# Current_Sense_2.net
KiCad netlist of a schematic drawn in Altium Designer
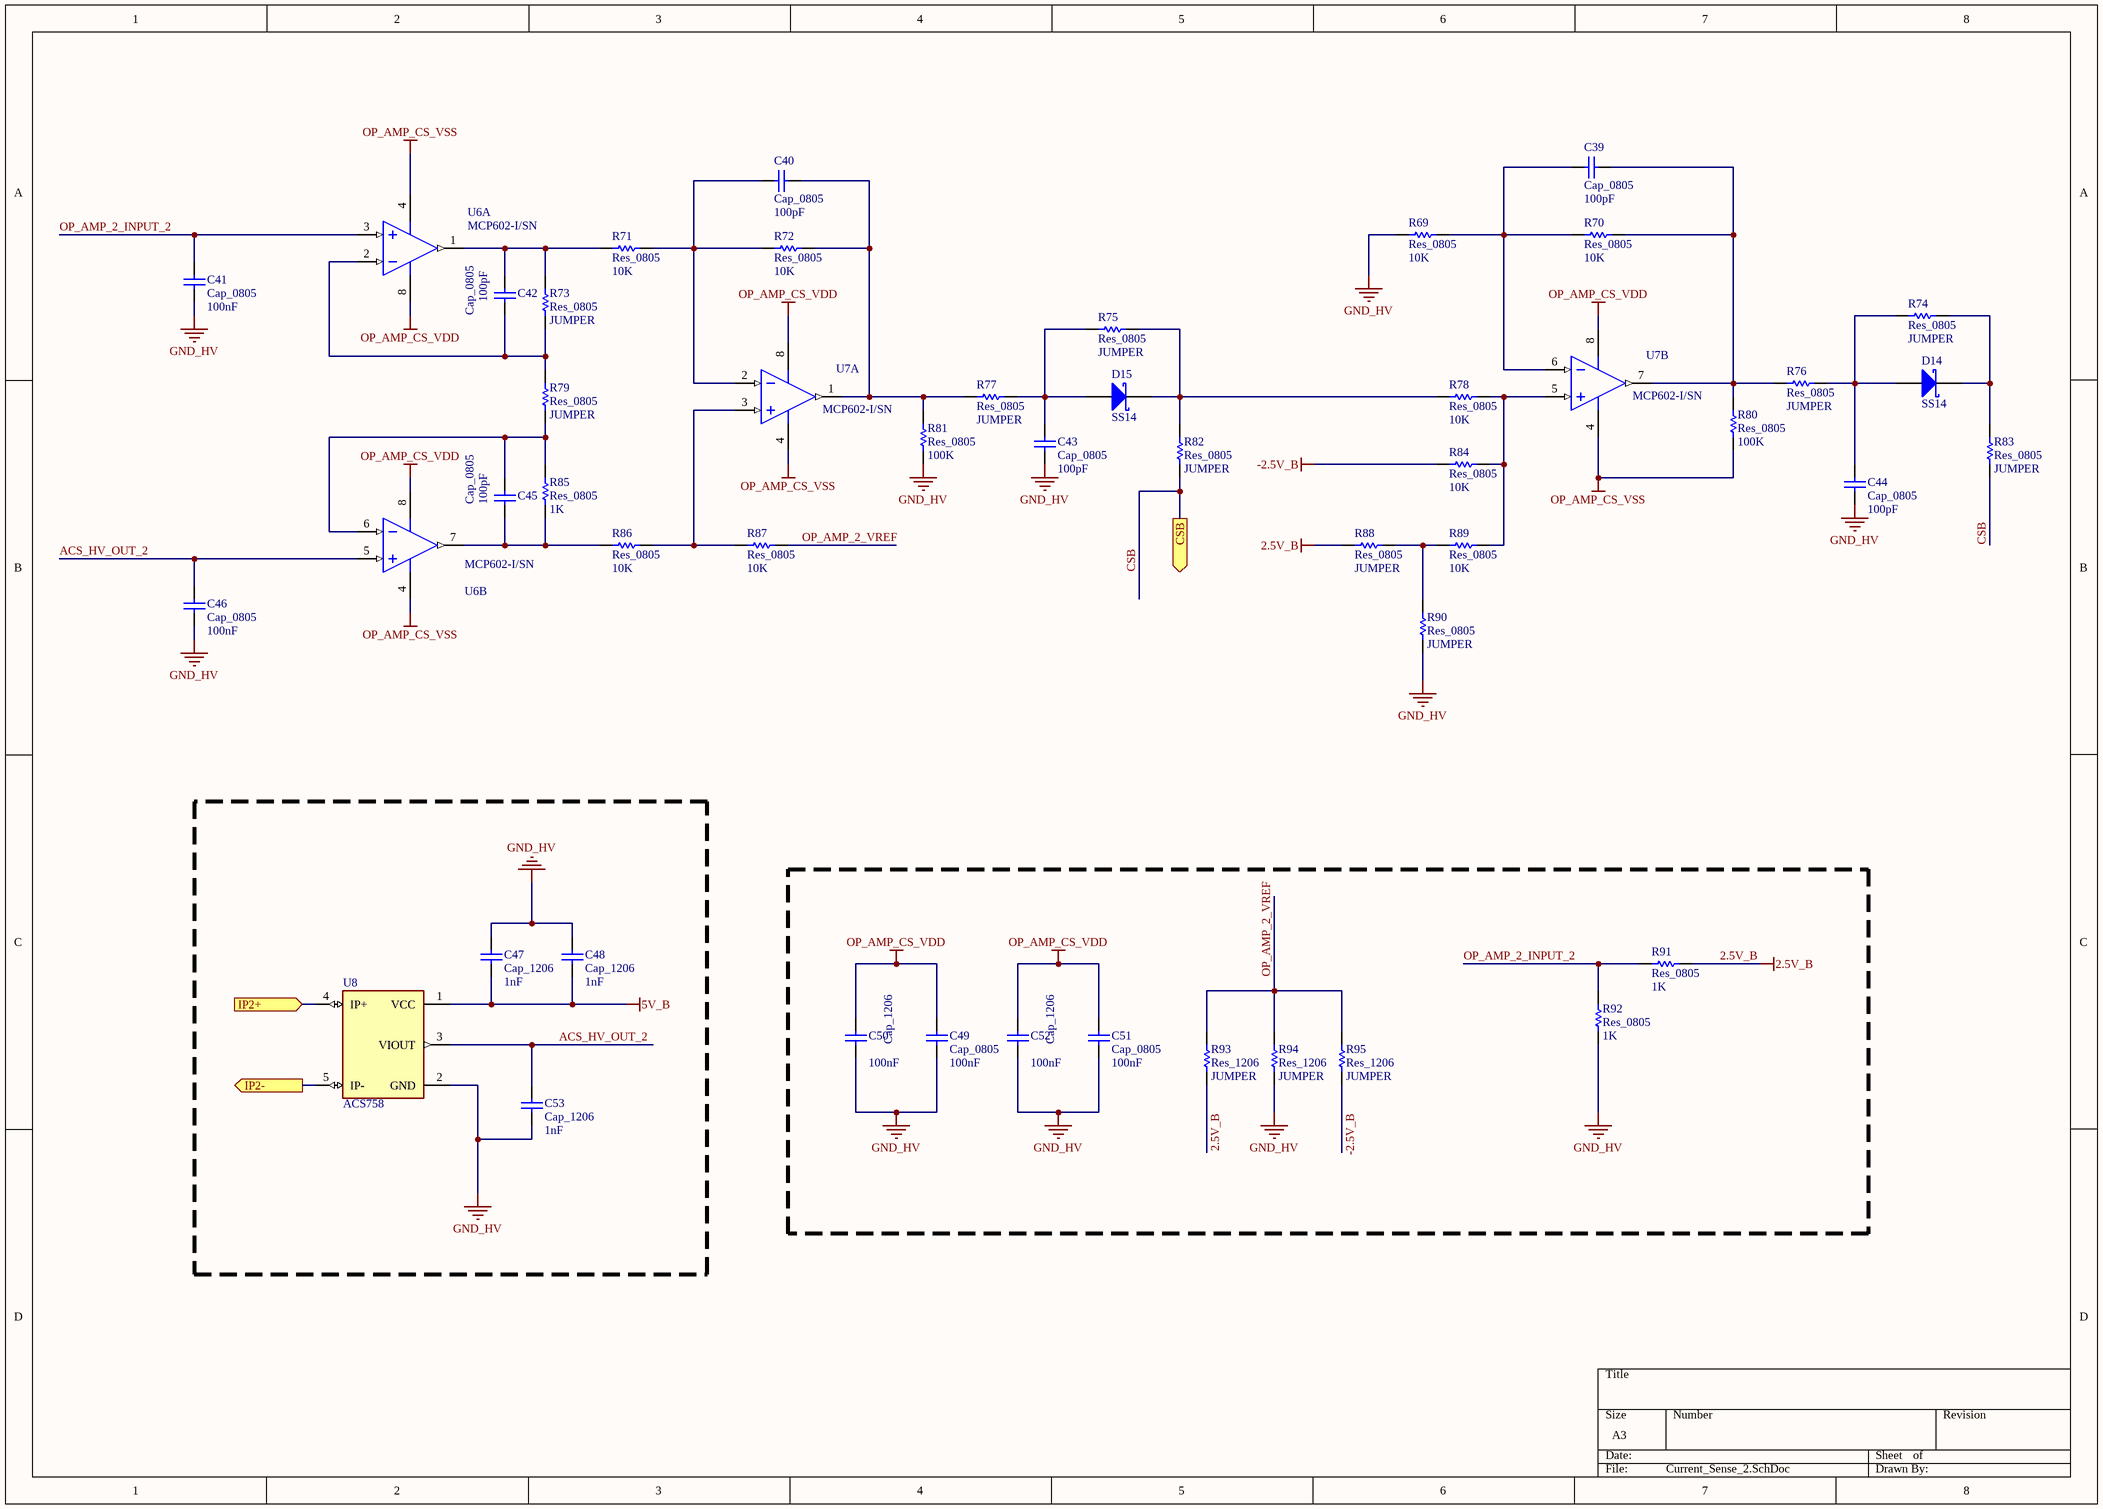
[diagram p0: Current_Sense_2.SchDoc]

(export (version "E")
  (design (tool "Eeschema 10.0.6"))
  (components
    (comp (ref "C39")
      (value "Cap_0805")
      (footprint "SMD-0805C")
      (description "Capacitor")
      (fields (field (name "ALTIUM_VALUE") "100pF") (field (name "PUBLISHER") "Altium Limited"))
      (libsource (lib "Miscellaneous Devices") (part "Cap"))
    )
    (comp (ref "C40")
      (value "Cap_0805")
      (footprint "SMD-0805C")
      (description "Capacitor")
      (fields (field (name "ALTIUM_VALUE") "100pF") (field (name "PUBLISHER") "Altium Limited"))
      (libsource (lib "Miscellaneous Devices") (part "Cap"))
    )
    (comp (ref "C41")
      (value "Cap_0805")
      (footprint "SMD-0805C")
      (description "Capacitor")
      (fields (field (name "ALTIUM_VALUE") "100nF") (field (name "PUBLISHER") "Altium Limited"))
      (libsource (lib "Miscellaneous Devices") (part "Cap"))
    )
    (comp (ref "C42")
      (value "Cap_0805")
      (footprint "SMD-0805C")
      (description "Capacitor")
      (fields (field (name "ALTIUM_VALUE") "100pF") (field (name "PUBLISHER") "Altium Limited"))
      (libsource (lib "Miscellaneous Devices") (part "Cap"))
    )
    (comp (ref "C43")
      (value "Cap_0805")
      (footprint "SMD-0805C")
      (description "Capacitor")
      (fields (field (name "ALTIUM_VALUE") "100pF") (field (name "PUBLISHER") "Altium Limited"))
      (libsource (lib "Miscellaneous Devices") (part "Cap"))
    )
    (comp (ref "C44")
      (value "Cap_0805")
      (footprint "SMD-0805C")
      (description "Capacitor")
      (fields (field (name "ALTIUM_VALUE") "100pF") (field (name "PUBLISHER") "Altium Limited"))
      (libsource (lib "Miscellaneous Devices") (part "Cap"))
    )
    (comp (ref "C45")
      (value "Cap_0805")
      (footprint "SMD-0805C")
      (description "Capacitor")
      (fields (field (name "ALTIUM_VALUE") "100pF") (field (name "PUBLISHER") "Altium Limited"))
      (libsource (lib "Miscellaneous Devices") (part "Cap"))
    )
    (comp (ref "C46")
      (value "Cap_0805")
      (footprint "SMD-0805C")
      (description "Capacitor")
      (fields (field (name "ALTIUM_VALUE") "100nF") (field (name "PUBLISHER") "Altium Limited"))
      (libsource (lib "Miscellaneous Devices") (part "Cap"))
    )
    (comp (ref "C47")
      (value "Cap_1206")
      (footprint "SMD-1206C")
      (description "Capacitor")
      (fields (field (name "ALTIUM_VALUE") "1nF") (field (name "PUBLISHER") "Altium Limited"))
      (libsource (lib "Miscellaneous Devices") (part "Cap"))
    )
    (comp (ref "C48")
      (value "Cap_1206")
      (footprint "SMD-1206C")
      (description "Capacitor")
      (fields (field (name "ALTIUM_VALUE") "1nF") (field (name "PUBLISHER") "Altium Limited"))
      (libsource (lib "Miscellaneous Devices") (part "Cap"))
    )
    (comp (ref "C49")
      (value "Cap_0805")
      (footprint "SMD-0805C")
      (description "Capacitor")
      (fields (field (name "ALTIUM_VALUE") "100nF") (field (name "PUBLISHER") "Altium Limited"))
      (libsource (lib "Miscellaneous Devices") (part "Cap"))
    )
    (comp (ref "C50")
      (value "Cap_1206")
      (footprint "SMD-1206C")
      (description "Capacitor")
      (fields (field (name "ALTIUM_VALUE") "100nF") (field (name "PUBLISHER") "Altium Limited"))
      (libsource (lib "Miscellaneous Devices") (part "Cap"))
    )
    (comp (ref "C51")
      (value "Cap_0805")
      (footprint "SMD-0805C")
      (description "Capacitor")
      (fields (field (name "ALTIUM_VALUE") "100nF") (field (name "PUBLISHER") "Altium Limited"))
      (libsource (lib "Miscellaneous Devices") (part "Cap"))
    )
    (comp (ref "C52")
      (value "Cap_1206")
      (footprint "SMD-1206C")
      (description "Capacitor")
      (fields (field (name "ALTIUM_VALUE") "100nF") (field (name "PUBLISHER") "Altium Limited"))
      (libsource (lib "Miscellaneous Devices") (part "Cap"))
    )
    (comp (ref "C53")
      (value "Cap_1206")
      (footprint "SMD-1206C")
      (description "Capacitor")
      (fields (field (name "ALTIUM_VALUE") "1nF") (field (name "PUBLISHER") "Altium Limited"))
      (libsource (lib "Miscellaneous Devices") (part "Cap"))
    )
    (comp (ref "D14")
      (value "SS14")
      (footprint "DIOM4226X22N")
      (description "Schottky Rectifier, 1.1 W, -65 to 125 degC, 2-Pin SMD, RoHS, Tape and Reel")
      (fields (field (name "MANUFACTURER") "Fairchild"))
      (libsource (lib "PFC_Stage") (part "SS14"))
    )
    (comp (ref "D15")
      (value "SS14")
      (footprint "DIOM4226X22N")
      (description "Schottky Rectifier, 1.1 W, -65 to 125 degC, 2-Pin SMD, RoHS, Tape and Reel")
      (fields (field (name "MANUFACTURER") "Fairchild"))
      (libsource (lib "PFC_Stage") (part "SS14"))
    )
    (comp (ref "R69")
      (value "Res_0805")
      (footprint "WRIS-KSKE_0805_H=0.6mm")
      (description "Resistor")
      (fields (field (name "ALTIUM_VALUE") "10K") (field (name "PUBLISHER") "Altium Limited"))
      (libsource (lib "Miscellaneous Devices") (part "Res1"))
    )
    (comp (ref "R70")
      (value "Res_0805")
      (footprint "WRIS-KSKE_0805_H=0.6mm")
      (description "Resistor")
      (fields (field (name "ALTIUM_VALUE") "10K") (field (name "PUBLISHER") "Altium Limited"))
      (libsource (lib "Miscellaneous Devices") (part "Res1"))
    )
    (comp (ref "R71")
      (value "Res_0805")
      (footprint "WRIS-KSKE_0805_H=0.6mm")
      (description "Resistor")
      (fields (field (name "ALTIUM_VALUE") "10K") (field (name "PUBLISHER") "Altium Limited"))
      (libsource (lib "Miscellaneous Devices") (part "Res1"))
    )
    (comp (ref "R72")
      (value "Res_0805")
      (footprint "WRIS-KSKE_0805_H=0.6mm")
      (description "Resistor")
      (fields (field (name "ALTIUM_VALUE") "10K") (field (name "PUBLISHER") "Altium Limited"))
      (libsource (lib "Miscellaneous Devices") (part "Res1"))
    )
    (comp (ref "R73")
      (value "Res_0805")
      (footprint "WRIS-KSKE_0805_H=0.6mm")
      (description "Resistor")
      (fields (field (name "ALTIUM_VALUE") "JUMPER") (field (name "PUBLISHER") "Altium Limited"))
      (libsource (lib "Miscellaneous Devices") (part "Res1"))
    )
    (comp (ref "R74")
      (value "Res_0805")
      (footprint "WRIS-KSKE_0805_H=0.6mm")
      (description "Resistor")
      (fields (field (name "ALTIUM_VALUE") "JUMPER") (field (name "PUBLISHER") "Altium Limited"))
      (libsource (lib "Miscellaneous Devices") (part "Res1"))
    )
    (comp (ref "R75")
      (value "Res_0805")
      (footprint "WRIS-KSKE_0805_H=0.6mm")
      (description "Resistor")
      (fields (field (name "ALTIUM_VALUE") "JUMPER") (field (name "PUBLISHER") "Altium Limited"))
      (libsource (lib "Miscellaneous Devices") (part "Res1"))
    )
    (comp (ref "R76")
      (value "Res_0805")
      (footprint "WRIS-KSKE_0805_H=0.6mm")
      (description "Resistor")
      (fields (field (name "ALTIUM_VALUE") "JUMPER") (field (name "PUBLISHER") "Altium Limited"))
      (libsource (lib "Miscellaneous Devices") (part "Res1"))
    )
    (comp (ref "R77")
      (value "Res_0805")
      (footprint "WRIS-KSKE_0805_H=0.6mm")
      (description "Resistor")
      (fields (field (name "ALTIUM_VALUE") "JUMPER") (field (name "PUBLISHER") "Altium Limited"))
      (libsource (lib "Miscellaneous Devices") (part "Res1"))
    )
    (comp (ref "R78")
      (value "Res_0805")
      (footprint "WRIS-KSKE_0805_H=0.6mm")
      (description "Resistor")
      (fields (field (name "ALTIUM_VALUE") "10K") (field (name "PUBLISHER") "Altium Limited"))
      (libsource (lib "Miscellaneous Devices") (part "Res1"))
    )
    (comp (ref "R79")
      (value "Res_0805")
      (footprint "WRIS-KSKE_0805_H=0.6mm")
      (description "Resistor")
      (fields (field (name "ALTIUM_VALUE") "JUMPER") (field (name "PUBLISHER") "Altium Limited"))
      (libsource (lib "Miscellaneous Devices") (part "Res1"))
    )
    (comp (ref "R80")
      (value "Res_0805")
      (footprint "WRIS-KSKE_0805_H=0.6mm")
      (description "Resistor")
      (fields (field (name "ALTIUM_VALUE") "100K") (field (name "PUBLISHER") "Altium Limited"))
      (libsource (lib "Miscellaneous Devices") (part "Res1"))
    )
    (comp (ref "R81")
      (value "Res_0805")
      (footprint "WRIS-KSKE_0805_H=0.6mm")
      (description "Resistor")
      (fields (field (name "ALTIUM_VALUE") "100K") (field (name "PUBLISHER") "Altium Limited"))
      (libsource (lib "Miscellaneous Devices") (part "Res1"))
    )
    (comp (ref "R82")
      (value "Res_0805")
      (footprint "WRIS-KSKE_0805_H=0.6mm")
      (description "Resistor")
      (fields (field (name "ALTIUM_VALUE") "JUMPER") (field (name "PUBLISHER") "Altium Limited"))
      (libsource (lib "Miscellaneous Devices") (part "Res1"))
    )
    (comp (ref "R83")
      (value "Res_0805")
      (footprint "WRIS-KSKE_0805_H=0.6mm")
      (description "Resistor")
      (fields (field (name "ALTIUM_VALUE") "JUMPER") (field (name "PUBLISHER") "Altium Limited"))
      (libsource (lib "Miscellaneous Devices") (part "Res1"))
    )
    (comp (ref "R84")
      (value "Res_0805")
      (footprint "WRIS-KSKE_0805_H=0.6mm")
      (description "Resistor")
      (fields (field (name "ALTIUM_VALUE") "10K") (field (name "PUBLISHER") "Altium Limited"))
      (libsource (lib "Miscellaneous Devices") (part "Res1"))
    )
    (comp (ref "R85")
      (value "Res_0805")
      (footprint "WRIS-KSKE_0805_H=0.6mm")
      (description "Resistor")
      (fields (field (name "ALTIUM_VALUE") "1K") (field (name "PUBLISHER") "Altium Limited"))
      (libsource (lib "Miscellaneous Devices") (part "Res1"))
    )
    (comp (ref "R86")
      (value "Res_0805")
      (footprint "WRIS-KSKE_0805_H=0.6mm")
      (description "Resistor")
      (fields (field (name "ALTIUM_VALUE") "10K") (field (name "PUBLISHER") "Altium Limited"))
      (libsource (lib "Miscellaneous Devices") (part "Res1"))
    )
    (comp (ref "R87")
      (value "Res_0805")
      (footprint "WRIS-KSKE_0805_H=0.6mm")
      (description "Resistor")
      (fields (field (name "ALTIUM_VALUE") "10K") (field (name "PUBLISHER") "Altium Limited"))
      (libsource (lib "Miscellaneous Devices") (part "Res1"))
    )
    (comp (ref "R88")
      (value "Res_0805")
      (footprint "WRIS-KSKE_0805_H=0.6mm")
      (description "Resistor")
      (fields (field (name "ALTIUM_VALUE") "JUMPER") (field (name "PUBLISHER") "Altium Limited"))
      (libsource (lib "Miscellaneous Devices") (part "Res1"))
    )
    (comp (ref "R89")
      (value "Res_0805")
      (footprint "WRIS-KSKE_0805_H=0.6mm")
      (description "Resistor")
      (fields (field (name "ALTIUM_VALUE") "10K") (field (name "PUBLISHER") "Altium Limited"))
      (libsource (lib "Miscellaneous Devices") (part "Res1"))
    )
    (comp (ref "R90")
      (value "Res_0805")
      (footprint "WRIS-KSKE_0805_H=0.6mm")
      (description "Resistor")
      (fields (field (name "ALTIUM_VALUE") "JUMPER") (field (name "PUBLISHER") "Altium Limited"))
      (libsource (lib "Miscellaneous Devices") (part "Res1"))
    )
    (comp (ref "R91")
      (value "Res_0805")
      (footprint "WRIS-KSKE_0805_H=0.6mm")
      (description "Resistor")
      (fields (field (name "ALTIUM_VALUE") "1K") (field (name "PUBLISHER") "Altium Limited"))
      (libsource (lib "Miscellaneous Devices") (part "Res1"))
    )
    (comp (ref "R92")
      (value "Res_0805")
      (footprint "WRIS-KSKE_0805_H=0.6mm")
      (description "Resistor")
      (fields (field (name "ALTIUM_VALUE") "1K") (field (name "PUBLISHER") "Altium Limited"))
      (libsource (lib "Miscellaneous Devices") (part "Res1"))
    )
    (comp (ref "R93")
      (value "Res_1206")
      (footprint "WRIS-KSKE_1206_H=0.6mm")
      (description "Resistor")
      (fields (field (name "ALTIUM_VALUE") "JUMPER") (field (name "PUBLISHER") "Altium Limited"))
      (libsource (lib "Miscellaneous Devices") (part "Res1"))
    )
    (comp (ref "R94")
      (value "Res_1206")
      (footprint "WRIS-KSKE_1206_H=0.6mm")
      (description "Resistor")
      (fields (field (name "ALTIUM_VALUE") "JUMPER") (field (name "PUBLISHER") "Altium Limited"))
      (libsource (lib "Miscellaneous Devices") (part "Res1"))
    )
    (comp (ref "R95")
      (value "Res_1206")
      (footprint "WRIS-KSKE_1206_H=0.6mm")
      (description "Resistor")
      (fields (field (name "ALTIUM_VALUE") "JUMPER") (field (name "PUBLISHER") "Altium Limited"))
      (libsource (lib "Miscellaneous Devices") (part "Res1"))
    )
    (comp (ref "U6")
      (value "MCP602-I/SN")
      (footprint "SOIC127P570X175_HS-9N - No Thermal")
      (description "2.7V to 6.0V Single Supply CMOS Operational Amplifier, 8-Pin SOIC, Industrial Temperature")
      (libsource (lib "Power Board UCC28951") (part "MCP602_2"))
    )
    (comp (ref "U7")
      (value "MCP602-I/SN")
      (footprint "SOIC127P570X175_HS-9N - No Thermal")
      (description "2.7V to 6.0V Single Supply CMOS Operational Amplifier, 8-Pin SOIC, Industrial Temperature")
      (libsource (lib "Power Board UCC28951") (part "MCP602_2"))
    )
    (comp (ref "U8")
      (value "ACS758")
      (footprint "XDCR_ACS758")
      (description "Current Sensor 50A 1 Channel Hall Effect, Open Loop Unidirectional 5-CB Formed Leads, PFF")
      (fields (field (name "MF") "Allegro MicroSystems LLC"))
      (libsource (lib "PFC_Stage") (part "ACS758"))
    )
  )
  (nets
    (net (code "1") (name "-2.5V_B") (class "Default")
      (node (ref "R84") (pin "2") (pinfunction "2_2") (pintype "passive"))
      (node (ref "R95") (pin "1") (pinfunction "1_1") (pintype "passive"))
    )
    (net (code "2") (name "/ACS_HV_OUT_2") (class "Default")
      (node (ref "C46") (pin "2") (pinfunction "2_2") (pintype "passive"))
      (node (ref "C53") (pin "2") (pinfunction "2_2") (pintype "passive"))
      (node (ref "U6") (pin "5") (pinfunction "VINB+_5") (pintype "input"))
      (node (ref "U8") (pin "3") (pinfunction "VIOUT_3") (pintype "output"))
    )
    (net (code "3") (name "/CSB") (class "Default")
      (node (ref "R82") (pin "1") (pinfunction "1_1") (pintype "passive"))
      (node (ref "R83") (pin "1") (pinfunction "1_1") (pintype "passive"))
    )
    (net (code "4") (name "/IP2+") (class "Default")
      (node (ref "U8") (pin "4") (pinfunction "IP+_4") (pintype "bidirectional"))
    )
    (net (code "5") (name "/IP2-") (class "Default")
      (node (ref "U8") (pin "5") (pinfunction "IP-_5") (pintype "bidirectional"))
    )
    (net (code "6") (name "/OP_AMP_2_INPUT_2") (class "Default")
      (node (ref "C41") (pin "2") (pinfunction "2_2") (pintype "passive"))
      (node (ref "R91") (pin "1") (pinfunction "1_1") (pintype "passive"))
      (node (ref "R92") (pin "2") (pinfunction "2_2") (pintype "passive"))
      (node (ref "U6") (pin "3") (pinfunction "VINA+_3") (pintype "input"))
    )
    (net (code "7") (name "/OP_AMP_2_VREF") (class "Default")
      (node (ref "R87") (pin "1") (pinfunction "1_1") (pintype "passive"))
      (node (ref "R93") (pin "2") (pinfunction "2_2") (pintype "passive"))
      (node (ref "R94") (pin "2") (pinfunction "2_2") (pintype "passive"))
      (node (ref "R95") (pin "2") (pinfunction "2_2") (pintype "passive"))
    )
    (net (code "8") (name "2.5V_B") (class "Default")
      (node (ref "R88") (pin "1") (pinfunction "1_1") (pintype "passive"))
      (node (ref "R91") (pin "2") (pinfunction "2_2") (pintype "passive"))
      (node (ref "R93") (pin "1") (pinfunction "1_1") (pintype "passive"))
    )
    (net (code "9") (name "5V_B") (class "Default")
      (node (ref "C47") (pin "2") (pinfunction "2_2") (pintype "passive"))
      (node (ref "C48") (pin "2") (pinfunction "2_2") (pintype "passive"))
      (node (ref "U8") (pin "1") (pinfunction "VCC_1") (pintype "power_in"))
    )
    (net (code "10") (name "GND_HV") (class "Default")
      (node (ref "C41") (pin "1") (pinfunction "1_1") (pintype "passive"))
      (node (ref "C43") (pin "1") (pinfunction "1_1") (pintype "passive"))
      (node (ref "C44") (pin "1") (pinfunction "1_1") (pintype "passive"))
      (node (ref "C46") (pin "1") (pinfunction "1_1") (pintype "passive"))
      (node (ref "C47") (pin "1") (pinfunction "1_1") (pintype "passive"))
      (node (ref "C48") (pin "1") (pinfunction "1_1") (pintype "passive"))
      (node (ref "C49") (pin "1") (pinfunction "1_1") (pintype "passive"))
      (node (ref "C50") (pin "1") (pinfunction "1_1") (pintype "passive"))
      (node (ref "C51") (pin "1") (pinfunction "1_1") (pintype "passive"))
      (node (ref "C52") (pin "1") (pinfunction "1_1") (pintype "passive"))
      (node (ref "C53") (pin "1") (pinfunction "1_1") (pintype "passive"))
      (node (ref "R69") (pin "2") (pinfunction "2_2") (pintype "passive"))
      (node (ref "R81") (pin "2") (pinfunction "2_2") (pintype "passive"))
      (node (ref "R90") (pin "1") (pinfunction "1_1") (pintype "passive"))
      (node (ref "R92") (pin "1") (pinfunction "1_1") (pintype "passive"))
      (node (ref "R94") (pin "1") (pinfunction "1_1") (pintype "passive"))
      (node (ref "U8") (pin "2") (pinfunction "GND_2") (pintype "power_in"))
    )
    (net (code "11") (name "Net-(D14-A)") (class "Default")
      (node (ref "C44") (pin "2") (pinfunction "2_2") (pintype "passive"))
      (node (ref "D14") (pin "2") (pinfunction "A_2") (pintype "passive"))
      (node (ref "R74") (pin "1") (pinfunction "1_1") (pintype "passive"))
      (node (ref "R76") (pin "2") (pinfunction "2_2") (pintype "passive"))
    )
    (net (code "12") (name "Net-(D14-K)") (class "Default")
      (node (ref "D14") (pin "1") (pinfunction "K_1") (pintype "passive"))
      (node (ref "R74") (pin "2") (pinfunction "2_2") (pintype "passive"))
      (node (ref "R83") (pin "2") (pinfunction "2_2") (pintype "passive"))
    )
    (net (code "13") (name "Net-(D15-A)") (class "Default")
      (node (ref "C43") (pin "2") (pinfunction "2_2") (pintype "passive"))
      (node (ref "D15") (pin "2") (pinfunction "A_2") (pintype "passive"))
      (node (ref "R75") (pin "1") (pinfunction "1_1") (pintype "passive"))
      (node (ref "R77") (pin "2") (pinfunction "2_2") (pintype "passive"))
    )
    (net (code "14") (name "Net-(D15-K)") (class "Default")
      (node (ref "D15") (pin "1") (pinfunction "K_1") (pintype "passive"))
      (node (ref "R75") (pin "2") (pinfunction "2_2") (pintype "passive"))
      (node (ref "R78") (pin "2") (pinfunction "2_2") (pintype "passive"))
      (node (ref "R82") (pin "2") (pinfunction "2_2") (pintype "passive"))
    )
    (net (code "15") (name "Net-(R88-Pad2)") (class "Default")
      (node (ref "R88") (pin "2") (pinfunction "2_2") (pintype "passive"))
      (node (ref "R89") (pin "2") (pinfunction "2_2") (pintype "passive"))
      (node (ref "R90") (pin "2") (pinfunction "2_2") (pintype "passive"))
    )
    (net (code "16") (name "Net-(U6A-VINA-)") (class "Default")
      (node (ref "C42") (pin "1") (pinfunction "1_1") (pintype "passive"))
      (node (ref "R73") (pin "1") (pinfunction "1_1") (pintype "passive"))
      (node (ref "R79") (pin "2") (pinfunction "2_2") (pintype "passive"))
      (node (ref "U6") (pin "2") (pinfunction "VINA-_2") (pintype "input"))
    )
    (net (code "17") (name "Net-(U6A-VOUTA)") (class "Default")
      (node (ref "C42") (pin "2") (pinfunction "2_2") (pintype "passive"))
      (node (ref "R71") (pin "2") (pinfunction "2_2") (pintype "passive"))
      (node (ref "R73") (pin "2") (pinfunction "2_2") (pintype "passive"))
      (node (ref "U6") (pin "1") (pinfunction "VOUTA_1") (pintype "output"))
    )
    (net (code "18") (name "Net-(U6B-VINB-)") (class "Default")
      (node (ref "C45") (pin "2") (pinfunction "2_2") (pintype "passive"))
      (node (ref "R79") (pin "1") (pinfunction "1_1") (pintype "passive"))
      (node (ref "R85") (pin "2") (pinfunction "2_2") (pintype "passive"))
      (node (ref "U6") (pin "6") (pinfunction "VINB-_6") (pintype "input"))
    )
    (net (code "19") (name "Net-(U6B-VOUTB)") (class "Default")
      (node (ref "C45") (pin "1") (pinfunction "1_1") (pintype "passive"))
      (node (ref "R85") (pin "1") (pinfunction "1_1") (pintype "passive"))
      (node (ref "R86") (pin "2") (pinfunction "2_2") (pintype "passive"))
      (node (ref "U6") (pin "7") (pinfunction "VOUTB_7") (pintype "output"))
    )
    (net (code "20") (name "Net-(U7A-VINA+)") (class "Default")
      (node (ref "R86") (pin "1") (pinfunction "1_1") (pintype "passive"))
      (node (ref "R87") (pin "2") (pinfunction "2_2") (pintype "passive"))
      (node (ref "U7") (pin "3") (pinfunction "VINA+_3") (pintype "input"))
    )
    (net (code "21") (name "Net-(U7A-VINA-)") (class "Default")
      (node (ref "C40") (pin "1") (pinfunction "1_1") (pintype "passive"))
      (node (ref "R71") (pin "1") (pinfunction "1_1") (pintype "passive"))
      (node (ref "R72") (pin "2") (pinfunction "2_2") (pintype "passive"))
      (node (ref "U7") (pin "2") (pinfunction "VINA-_2") (pintype "input"))
    )
    (net (code "22") (name "Net-(U7A-VOUTA)") (class "Default")
      (node (ref "C40") (pin "2") (pinfunction "2_2") (pintype "passive"))
      (node (ref "R72") (pin "1") (pinfunction "1_1") (pintype "passive"))
      (node (ref "R77") (pin "1") (pinfunction "1_1") (pintype "passive"))
      (node (ref "R81") (pin "1") (pinfunction "1_1") (pintype "passive"))
      (node (ref "U7") (pin "1") (pinfunction "VOUTA_1") (pintype "output"))
    )
    (net (code "23") (name "Net-(U7B-VINB+)") (class "Default")
      (node (ref "R78") (pin "1") (pinfunction "1_1") (pintype "passive"))
      (node (ref "R84") (pin "1") (pinfunction "1_1") (pintype "passive"))
      (node (ref "R89") (pin "1") (pinfunction "1_1") (pintype "passive"))
      (node (ref "U7") (pin "5") (pinfunction "VINB+_5") (pintype "input"))
    )
    (net (code "24") (name "Net-(U7B-VINB-)") (class "Default")
      (node (ref "C39") (pin "1") (pinfunction "1_1") (pintype "passive"))
      (node (ref "R69") (pin "1") (pinfunction "1_1") (pintype "passive"))
      (node (ref "R70") (pin "2") (pinfunction "2_2") (pintype "passive"))
      (node (ref "U7") (pin "6") (pinfunction "VINB-_6") (pintype "input"))
    )
    (net (code "25") (name "Net-(U7B-VOUTB)") (class "Default")
      (node (ref "C39") (pin "2") (pinfunction "2_2") (pintype "passive"))
      (node (ref "R70") (pin "1") (pinfunction "1_1") (pintype "passive"))
      (node (ref "R76") (pin "1") (pinfunction "1_1") (pintype "passive"))
      (node (ref "R80") (pin "1") (pinfunction "1_1") (pintype "passive"))
      (node (ref "U7") (pin "7") (pinfunction "VOUTB_7") (pintype "output"))
    )
    (net (code "26") (name "OP_AMP_CS_VDD") (class "Default")
      (node (ref "C49") (pin "2") (pinfunction "2_2") (pintype "passive"))
      (node (ref "C50") (pin "2") (pinfunction "2_2") (pintype "passive"))
      (node (ref "C51") (pin "2") (pinfunction "2_2") (pintype "passive"))
      (node (ref "C52") (pin "2") (pinfunction "2_2") (pintype "passive"))
      (node (ref "U6") (pin "8") (pinfunction "VDD_8") (pintype "power_in"))
      (node (ref "U7") (pin "8") (pinfunction "VDD_8") (pintype "power_in"))
    )
    (net (code "27") (name "OP_AMP_CS_VSS") (class "Default")
      (node (ref "R80") (pin "2") (pinfunction "2_2") (pintype "passive"))
      (node (ref "U6") (pin "4") (pinfunction "VSS_4") (pintype "power_in"))
      (node (ref "U7") (pin "4") (pinfunction "VSS_4") (pintype "power_in"))
    )
  )
)
